# PCIe_104.net
KiCad netlist of a schematic drawn in Altium Designer
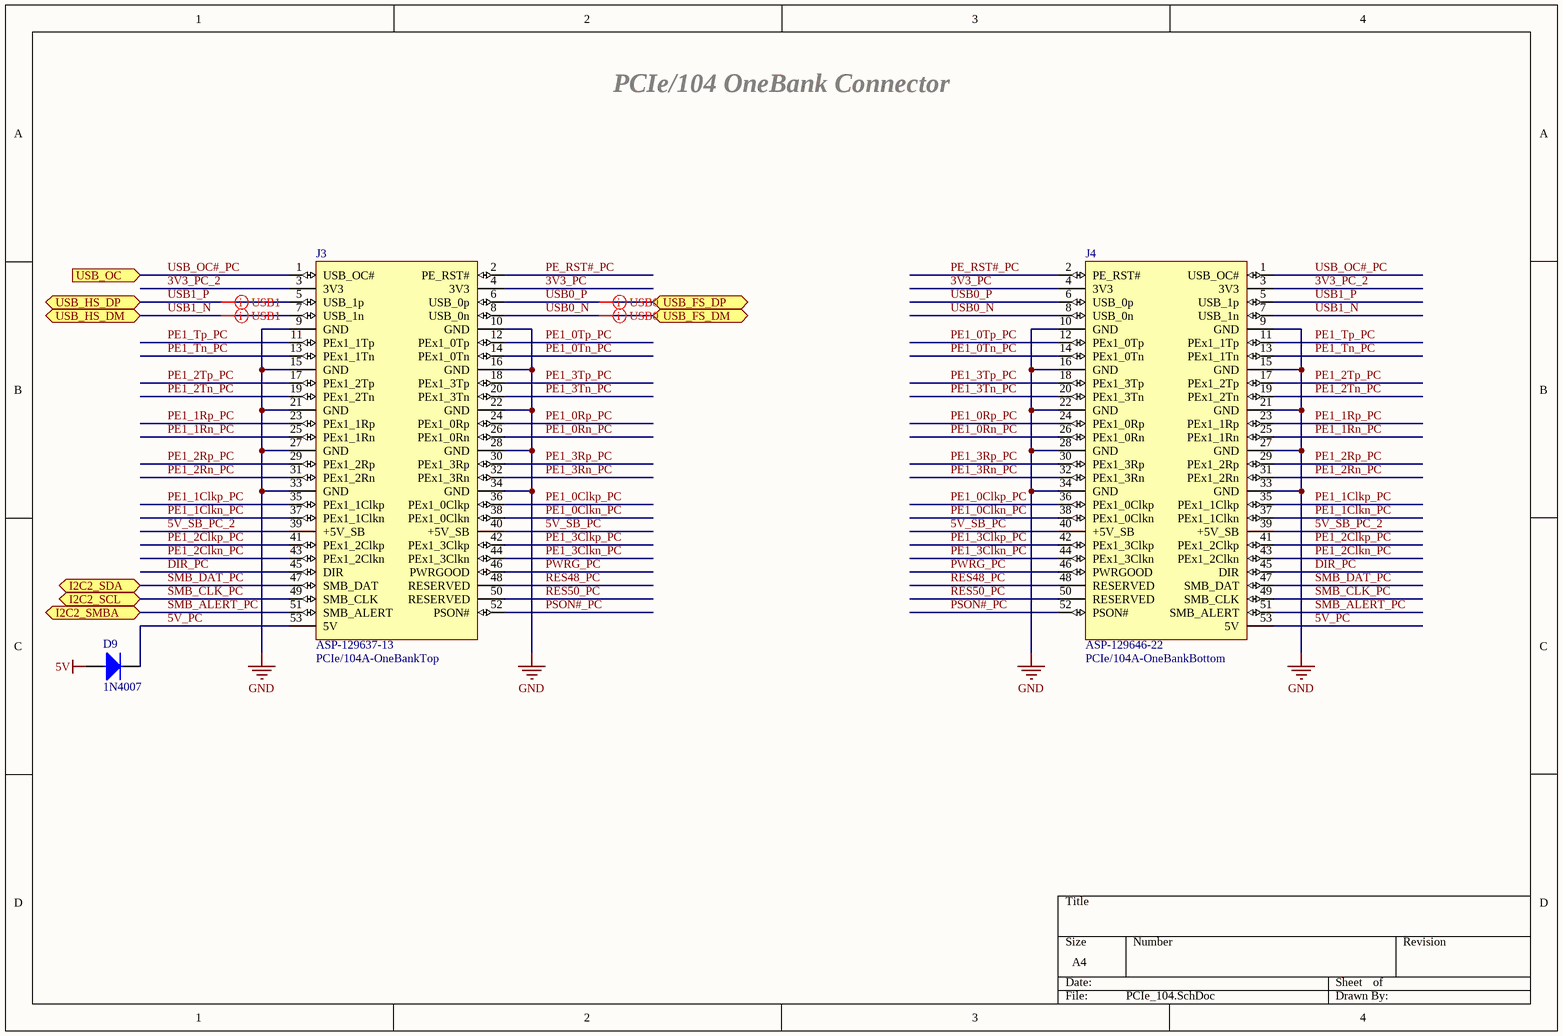
[diagram p0: PCIe_104.SchDoc]

(export (version "E")
  (design (tool "Eeschema 10.0.6"))
  (components
    (comp (ref "D9")
      (value "1N4007")
      (footprint "SMA (DO-214AC)")
      (description "Diodo")
      (libsource (lib "HW_Dron_V2") (part "Diode"))
    )
    (comp (ref "J3")
      (value "ASP-129637-13")
      (footprint "ASP-129637-13")
      (description "PCIe/104 Connector A, OneBank Top")
      (fields (field (name "ALTIUM_UNNAMED_1") "PCIe/104A-OneBankTop"))
      (libsource (lib "HW_Dron_V2") (part "PCIe/104A-OneBankTop"))
    )
    (comp (ref "J4")
      (value "ASP-129646-22")
      (footprint "ASP-129646-22")
      (description "PCIe/104 Connector A, OneBank Bottom")
      (fields (field (name "ALTIUM_UNNAMED_1") "PCIe/104A-OneBankBottom"))
      (libsource (lib "HW_Dron_V2") (part "PCIe/104A-OneBankBottom"))
    )
  )
  (nets
    (net (code "1") (name "/3V3_PC") (class "Default")
      (node (ref "J3") (pin "4") (pinfunction "3V3_4") (pintype "power_in"))
      (node (ref "J4") (pin "4") (pinfunction "3V3_4") (pintype "power_in"))
    )
    (net (code "2") (name "/3V3_PC_2") (class "Default")
      (node (ref "J3") (pin "3") (pinfunction "3V3_3") (pintype "power_in"))
      (node (ref "J4") (pin "3") (pinfunction "3V3_3") (pintype "power_in"))
    )
    (net (code "3") (name "/5V_PC") (class "Default")
      (node (ref "D9") (pin "2") (pinfunction "2_2") (pintype "passive"))
      (node (ref "J3") (pin "53") (pinfunction "5V_53") (pintype "power_in"))
      (node (ref "J4") (pin "53") (pinfunction "5V_53") (pintype "power_in"))
    )
    (net (code "4") (name "/5V_SB_PC") (class "Default")
      (node (ref "J3") (pin "40") (pinfunction "+5V_SB_40") (pintype "power_in"))
      (node (ref "J4") (pin "40") (pinfunction "+5V_SB_40") (pintype "power_in"))
    )
    (net (code "5") (name "/5V_SB_PC_2") (class "Default")
      (node (ref "J3") (pin "39") (pinfunction "+5V_SB_39") (pintype "power_in"))
      (node (ref "J4") (pin "39") (pinfunction "+5V_SB_39") (pintype "power_in"))
    )
    (net (code "6") (name "/DIR_PC") (class "Default")
      (node (ref "J3") (pin "45") (pinfunction "DIR_45") (pintype "bidirectional"))
      (node (ref "J4") (pin "45") (pinfunction "DIR_45") (pintype "bidirectional"))
    )
    (net (code "7") (name "/PE1_0Clkn_PC") (class "Default")
      (node (ref "J3") (pin "38") (pinfunction "PEx1_0Clkn_38") (pintype "bidirectional"))
      (node (ref "J4") (pin "38") (pinfunction "PEx1_0Clkn_38") (pintype "bidirectional"))
    )
    (net (code "8") (name "/PE1_0Clkp_PC") (class "Default")
      (node (ref "J3") (pin "36") (pinfunction "PEx1_0Clkp_36") (pintype "bidirectional"))
      (node (ref "J4") (pin "36") (pinfunction "PEx1_0Clkp_36") (pintype "bidirectional"))
    )
    (net (code "9") (name "/PE1_0Rn_PC") (class "Default")
      (node (ref "J3") (pin "26") (pinfunction "PEx1_0Rn_26") (pintype "bidirectional"))
      (node (ref "J4") (pin "26") (pinfunction "PEx1_0Rn_26") (pintype "bidirectional"))
    )
    (net (code "10") (name "/PE1_0Rp_PC") (class "Default")
      (node (ref "J3") (pin "24") (pinfunction "PEx1_0Rp_24") (pintype "bidirectional"))
      (node (ref "J4") (pin "24") (pinfunction "PEx1_0Rp_24") (pintype "bidirectional"))
    )
    (net (code "11") (name "/PE1_0Tn_PC") (class "Default")
      (node (ref "J3") (pin "14") (pinfunction "PEx1_0Tn_14") (pintype "bidirectional"))
      (node (ref "J4") (pin "14") (pinfunction "PEx1_0Tn_14") (pintype "bidirectional"))
    )
    (net (code "12") (name "/PE1_0Tp_PC") (class "Default")
      (node (ref "J3") (pin "12") (pinfunction "PEx1_0Tp_12") (pintype "bidirectional"))
      (node (ref "J4") (pin "12") (pinfunction "PEx1_0Tp_12") (pintype "bidirectional"))
    )
    (net (code "13") (name "/PE1_1Clkn_PC") (class "Default")
      (node (ref "J3") (pin "37") (pinfunction "PEx1_1Clkn_37") (pintype "bidirectional"))
      (node (ref "J4") (pin "37") (pinfunction "PEx1_1Clkn_37") (pintype "bidirectional"))
    )
    (net (code "14") (name "/PE1_1Clkp_PC") (class "Default")
      (node (ref "J3") (pin "35") (pinfunction "PEx1_1Clkp_35") (pintype "bidirectional"))
      (node (ref "J4") (pin "35") (pinfunction "PEx1_1Clkp_35") (pintype "bidirectional"))
    )
    (net (code "15") (name "/PE1_1Rn_PC") (class "Default")
      (node (ref "J3") (pin "25") (pinfunction "PEx1_1Rn_25") (pintype "bidirectional"))
      (node (ref "J4") (pin "25") (pinfunction "PEx1_1Rn_25") (pintype "bidirectional"))
    )
    (net (code "16") (name "/PE1_1Rp_PC") (class "Default")
      (node (ref "J3") (pin "23") (pinfunction "PEx1_1Rp_23") (pintype "bidirectional"))
      (node (ref "J4") (pin "23") (pinfunction "PEx1_1Rp_23") (pintype "bidirectional"))
    )
    (net (code "17") (name "/PE1_2Clkn_PC") (class "Default")
      (node (ref "J3") (pin "43") (pinfunction "PEx1_2Clkn_43") (pintype "bidirectional"))
      (node (ref "J4") (pin "43") (pinfunction "PEx1_2Clkn_43") (pintype "bidirectional"))
    )
    (net (code "18") (name "/PE1_2Clkp_PC") (class "Default")
      (node (ref "J3") (pin "41") (pinfunction "PEx1_2Clkp_41") (pintype "bidirectional"))
      (node (ref "J4") (pin "41") (pinfunction "PEx1_2Clkp_41") (pintype "bidirectional"))
    )
    (net (code "19") (name "/PE1_2Rn_PC") (class "Default")
      (node (ref "J3") (pin "31") (pinfunction "PEx1_2Rn_31") (pintype "bidirectional"))
      (node (ref "J4") (pin "31") (pinfunction "PEx1_2Rn_31") (pintype "bidirectional"))
    )
    (net (code "20") (name "/PE1_2Rp_PC") (class "Default")
      (node (ref "J3") (pin "29") (pinfunction "PEx1_2Rp_29") (pintype "bidirectional"))
      (node (ref "J4") (pin "29") (pinfunction "PEx1_2Rp_29") (pintype "bidirectional"))
    )
    (net (code "21") (name "/PE1_2Tn_PC") (class "Default")
      (node (ref "J3") (pin "19") (pinfunction "PEx1_2Tn_19") (pintype "bidirectional"))
      (node (ref "J4") (pin "19") (pinfunction "PEx1_2Tn_19") (pintype "bidirectional"))
    )
    (net (code "22") (name "/PE1_2Tp_PC") (class "Default")
      (node (ref "J3") (pin "17") (pinfunction "PEx1_2Tp_17") (pintype "bidirectional"))
      (node (ref "J4") (pin "17") (pinfunction "PEx1_2Tp_17") (pintype "bidirectional"))
    )
    (net (code "23") (name "/PE1_3Clkn_PC") (class "Default")
      (node (ref "J3") (pin "44") (pinfunction "PEx1_3Clkn_44") (pintype "bidirectional"))
      (node (ref "J4") (pin "44") (pinfunction "PEx1_3Clkn_44") (pintype "bidirectional"))
    )
    (net (code "24") (name "/PE1_3Clkp_PC") (class "Default")
      (node (ref "J3") (pin "42") (pinfunction "PEx1_3Clkp_42") (pintype "bidirectional"))
      (node (ref "J4") (pin "42") (pinfunction "PEx1_3Clkp_42") (pintype "bidirectional"))
    )
    (net (code "25") (name "/PE1_3Rn_PC") (class "Default")
      (node (ref "J3") (pin "32") (pinfunction "PEx1_3Rn_32") (pintype "bidirectional"))
      (node (ref "J4") (pin "32") (pinfunction "PEx1_3Rn_32") (pintype "bidirectional"))
    )
    (net (code "26") (name "/PE1_3Rp_PC") (class "Default")
      (node (ref "J3") (pin "30") (pinfunction "PEx1_3Rp_30") (pintype "bidirectional"))
      (node (ref "J4") (pin "30") (pinfunction "PEx1_3Rp_30") (pintype "bidirectional"))
    )
    (net (code "27") (name "/PE1_3Tn_PC") (class "Default")
      (node (ref "J3") (pin "20") (pinfunction "PEx1_3Tn_20") (pintype "bidirectional"))
      (node (ref "J4") (pin "20") (pinfunction "PEx1_3Tn_20") (pintype "bidirectional"))
    )
    (net (code "28") (name "/PE1_3Tp_PC") (class "Default")
      (node (ref "J3") (pin "18") (pinfunction "PEx1_3Tp_18") (pintype "bidirectional"))
      (node (ref "J4") (pin "18") (pinfunction "PEx1_3Tp_18") (pintype "bidirectional"))
    )
    (net (code "29") (name "/PE1_Tn_PC") (class "Default")
      (node (ref "J3") (pin "13") (pinfunction "PEx1_1Tn_13") (pintype "bidirectional"))
      (node (ref "J4") (pin "13") (pinfunction "PEx1_1Tn_13") (pintype "bidirectional"))
    )
    (net (code "30") (name "/PE1_Tp_PC") (class "Default")
      (node (ref "J3") (pin "11") (pinfunction "PEx1_1Tp_11") (pintype "bidirectional"))
      (node (ref "J4") (pin "11") (pinfunction "PEx1_1Tp_11") (pintype "bidirectional"))
    )
    (net (code "31") (name "/PE_RST#_PC") (class "Default")
      (node (ref "J3") (pin "2") (pinfunction "PE_RST#_2") (pintype "bidirectional"))
      (node (ref "J4") (pin "2") (pinfunction "PE_RST#_2") (pintype "bidirectional"))
    )
    (net (code "32") (name "/PSON#_PC") (class "Default")
      (node (ref "J3") (pin "52") (pinfunction "PSON#_52") (pintype "bidirectional"))
      (node (ref "J4") (pin "52") (pinfunction "PSON#_52") (pintype "bidirectional"))
    )
    (net (code "33") (name "/PWRG_PC") (class "Default")
      (node (ref "J3") (pin "46") (pinfunction "PWRGOOD_46") (pintype "bidirectional"))
      (node (ref "J4") (pin "46") (pinfunction "PWRGOOD_46") (pintype "bidirectional"))
    )
    (net (code "34") (name "/RES48_PC") (class "Default")
      (node (ref "J3") (pin "48") (pinfunction "RESERVED_48") (pintype "tri_state"))
      (node (ref "J4") (pin "48") (pinfunction "RESERVED_48") (pintype "tri_state"))
    )
    (net (code "35") (name "/RES50_PC") (class "Default")
      (node (ref "J3") (pin "50") (pinfunction "RESERVED_50") (pintype "tri_state"))
      (node (ref "J4") (pin "50") (pinfunction "RESERVED_50") (pintype "tri_state"))
    )
    (net (code "36") (name "/SMB_ALERT_PC") (class "Default")
      (node (ref "J3") (pin "51") (pinfunction "SMB_ALERT_51") (pintype "bidirectional"))
      (node (ref "J4") (pin "51") (pinfunction "SMB_ALERT_51") (pintype "bidirectional"))
    )
    (net (code "37") (name "/SMB_CLK_PC") (class "Default")
      (node (ref "J3") (pin "49") (pinfunction "SMB_CLK_49") (pintype "bidirectional"))
      (node (ref "J4") (pin "49") (pinfunction "SMB_CLK_49") (pintype "bidirectional"))
    )
    (net (code "38") (name "/SMB_DAT_PC") (class "Default")
      (node (ref "J3") (pin "47") (pinfunction "SMB_DAT_47") (pintype "bidirectional"))
      (node (ref "J4") (pin "47") (pinfunction "SMB_DAT_47") (pintype "bidirectional"))
    )
    (net (code "39") (name "/USB0_N") (class "Default")
      (node (ref "J3") (pin "8") (pinfunction "USB_0n_8") (pintype "bidirectional"))
      (node (ref "J4") (pin "8") (pinfunction "USB_0n_8") (pintype "bidirectional"))
    )
    (net (code "40") (name "/USB0_P") (class "Default")
      (node (ref "J3") (pin "6") (pinfunction "USB_0p_6") (pintype "bidirectional"))
      (node (ref "J4") (pin "6") (pinfunction "USB_0p_6") (pintype "bidirectional"))
    )
    (net (code "41") (name "/USB1_N") (class "Default")
      (node (ref "J3") (pin "7") (pinfunction "USB_1n_7") (pintype "bidirectional"))
      (node (ref "J4") (pin "7") (pinfunction "USB_1n_7") (pintype "bidirectional"))
    )
    (net (code "42") (name "/USB1_P") (class "Default")
      (node (ref "J3") (pin "5") (pinfunction "USB_1p_5") (pintype "bidirectional"))
      (node (ref "J4") (pin "5") (pinfunction "USB_1p_5") (pintype "bidirectional"))
    )
    (net (code "43") (name "/USB_OC#_PC") (class "Default")
      (node (ref "J3") (pin "1") (pinfunction "USB_OC#_1") (pintype "bidirectional"))
      (node (ref "J4") (pin "1") (pinfunction "USB_OC#_1") (pintype "bidirectional"))
    )
    (net (code "44") (name "5V") (class "Default")
      (node (ref "D9") (pin "1") (pinfunction "1_1") (pintype "passive"))
    )
    (net (code "45") (name "GND") (class "Default")
      (node (ref "J3") (pin "10") (pinfunction "GND_10") (pintype "power_in"))
      (node (ref "J3") (pin "15") (pinfunction "GND_15") (pintype "power_in"))
      (node (ref "J3") (pin "16") (pinfunction "GND_16") (pintype "power_in"))
      (node (ref "J3") (pin "21") (pinfunction "GND_21") (pintype "power_in"))
      (node (ref "J3") (pin "22") (pinfunction "GND_22") (pintype "power_in"))
      (node (ref "J3") (pin "27") (pinfunction "GND_27") (pintype "power_in"))
      (node (ref "J3") (pin "28") (pinfunction "GND_28") (pintype "power_in"))
      (node (ref "J3") (pin "33") (pinfunction "GND_33") (pintype "power_in"))
      (node (ref "J3") (pin "34") (pinfunction "GND_34") (pintype "power_in"))
      (node (ref "J3") (pin "9") (pinfunction "GND_9") (pintype "power_in"))
      (node (ref "J4") (pin "10") (pinfunction "GND_10") (pintype "power_in"))
      (node (ref "J4") (pin "15") (pinfunction "GND_15") (pintype "power_in"))
      (node (ref "J4") (pin "16") (pinfunction "GND_16") (pintype "power_in"))
      (node (ref "J4") (pin "21") (pinfunction "GND_21") (pintype "power_in"))
      (node (ref "J4") (pin "22") (pinfunction "GND_22") (pintype "power_in"))
      (node (ref "J4") (pin "27") (pinfunction "GND_27") (pintype "power_in"))
      (node (ref "J4") (pin "28") (pinfunction "GND_28") (pintype "power_in"))
      (node (ref "J4") (pin "33") (pinfunction "GND_33") (pintype "power_in"))
      (node (ref "J4") (pin "34") (pinfunction "GND_34") (pintype "power_in"))
      (node (ref "J4") (pin "9") (pinfunction "GND_9") (pintype "power_in"))
    )
  )
)
